# servocontroller.net
KiCad netlist of a schematic drawn in EAGLE
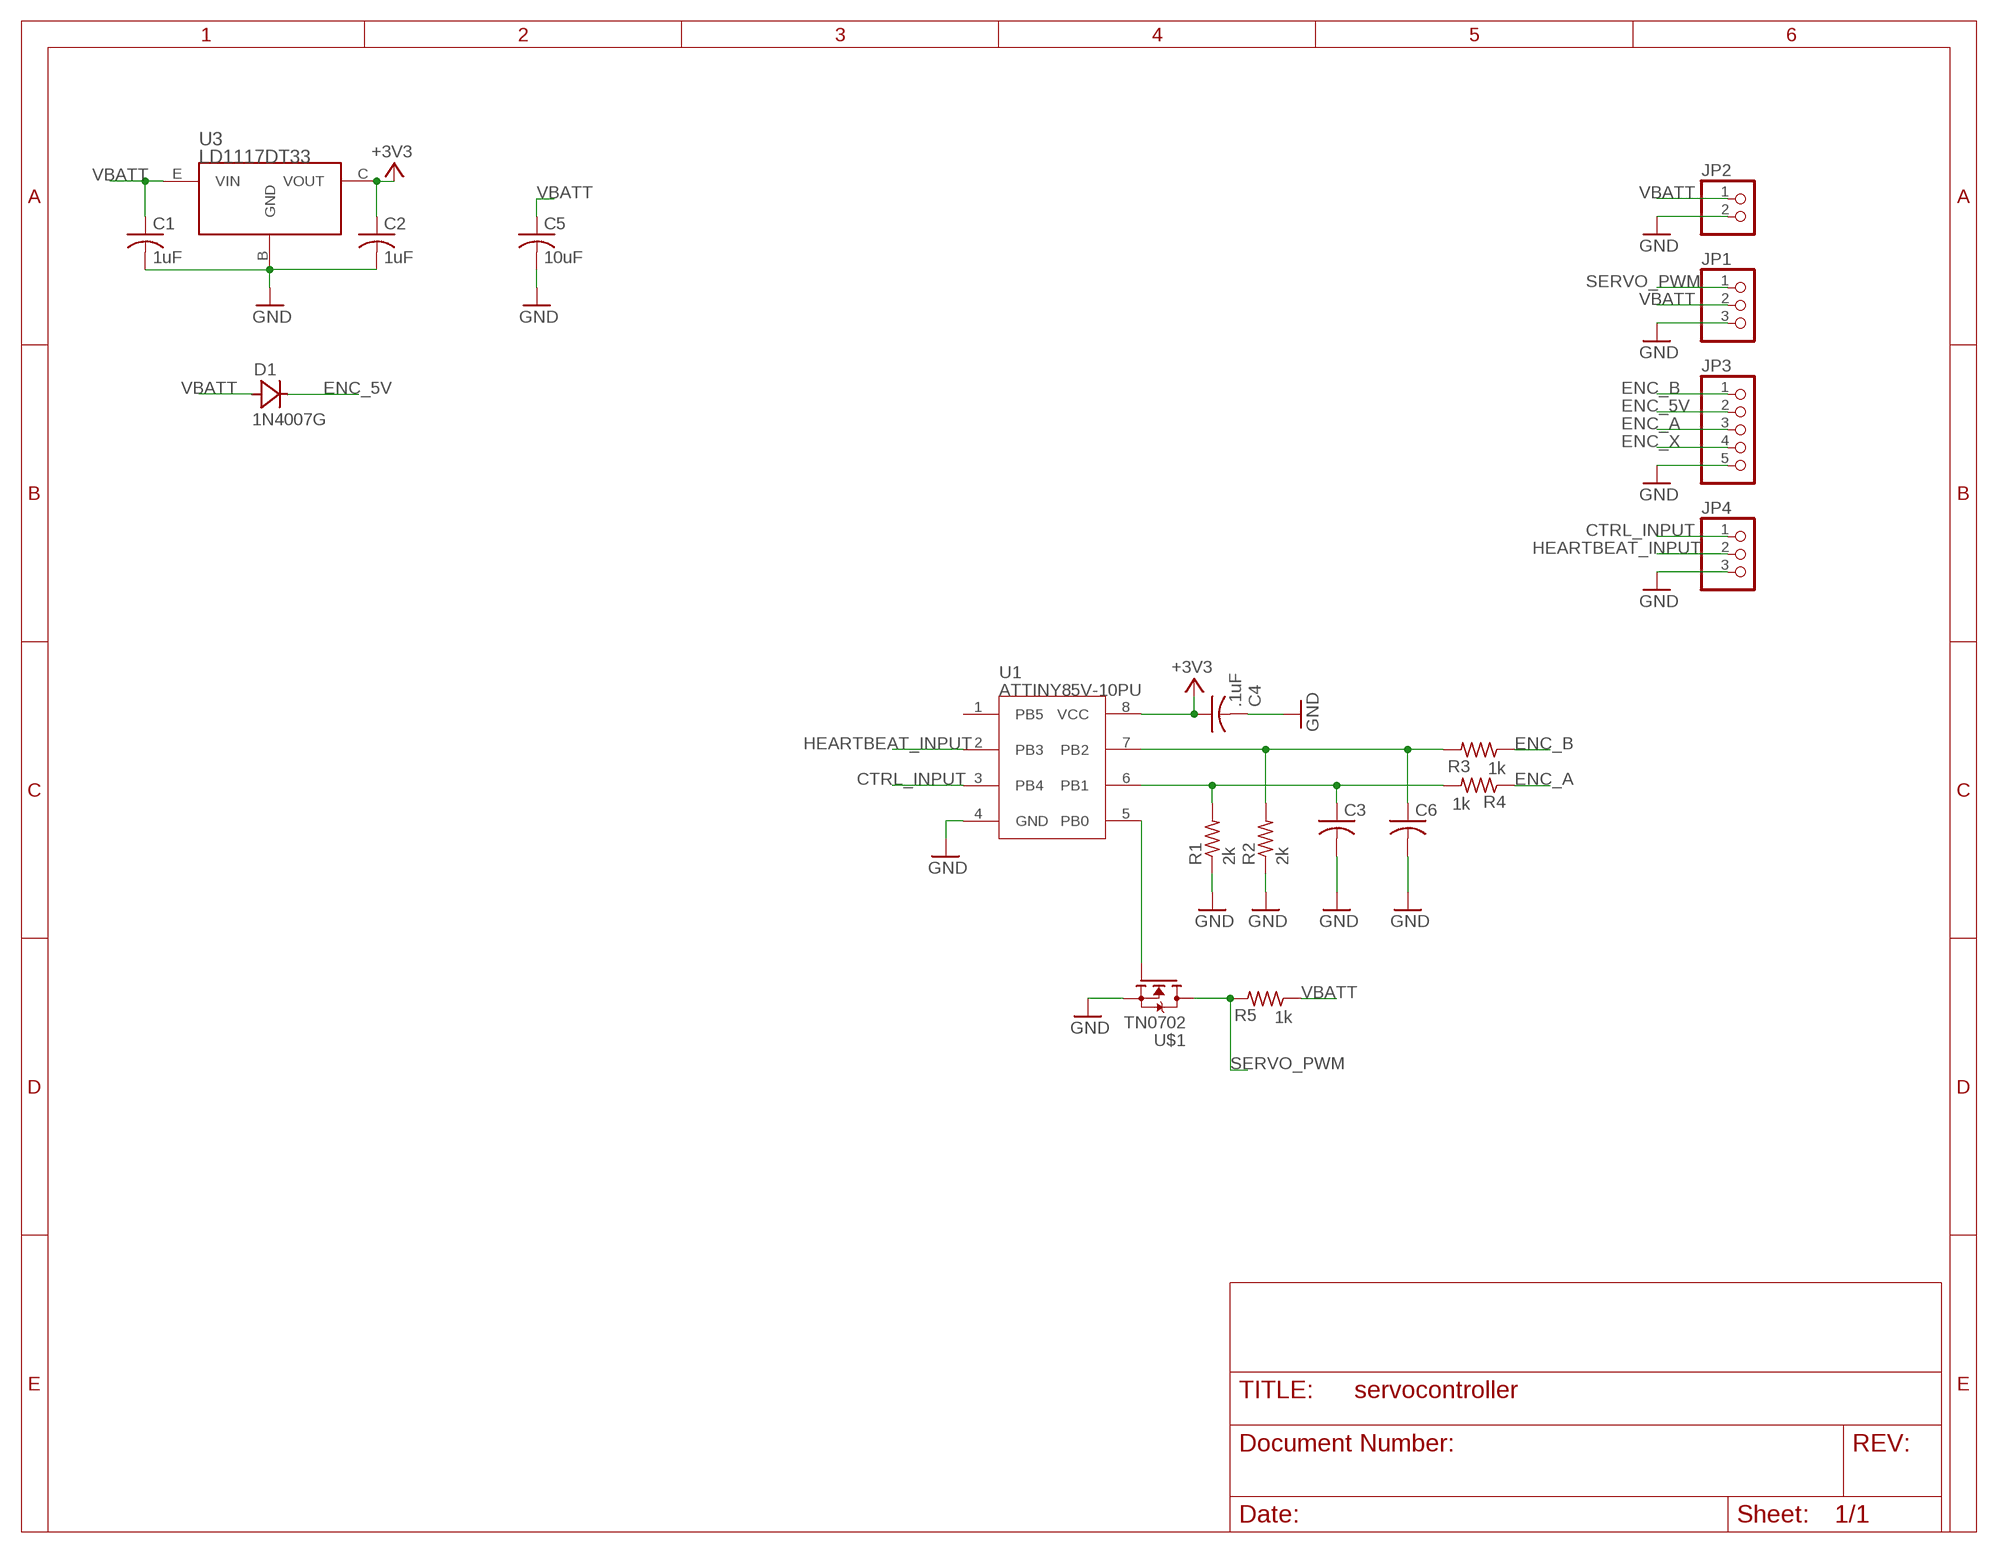
[diagram p0: schematic, sheet 1]

(export (version "E")
  (design (tool "Eeschema 10.0.6"))
  (components
    (comp (ref "C1")
      (value "1uF")
      (footprint "eagle-import:C0805")
      (libsource (lib "eagle-import") (part "C-USC0805"))
    )
    (comp (ref "C2")
      (value "1uF")
      (footprint "eagle-import:C0805")
      (libsource (lib "eagle-import") (part "C-USC0805"))
    )
    (comp (ref "C3")
      (value "C-USC0805")
      (footprint "eagle-import:C0805")
      (libsource (lib "eagle-import") (part "C-USC0805"))
    )
    (comp (ref "C4")
      (value ".1uF")
      (footprint "eagle-import:C0805")
      (libsource (lib "eagle-import") (part "C-USC0805"))
    )
    (comp (ref "C5")
      (value "10uF")
      (footprint "eagle-import:C0805")
      (libsource (lib "eagle-import") (part "C-USC0805"))
    )
    (comp (ref "C6")
      (value "C-USC0805")
      (footprint "eagle-import:C0805")
      (libsource (lib "eagle-import") (part "C-USC0805"))
    )
    (comp (ref "D1")
      (value "1N4007G")
      (footprint "eagle-import:DO35-7A")
      (libsource (lib "eagle-import") (part "1N4007G"))
    )
    (comp (ref "JP1")
      (value "PINHD-1X3")
      (footprint "eagle-import:1X03")
      (libsource (lib "eagle-import") (part "PINHD-1X3"))
    )
    (comp (ref "JP2")
      (value "PINHD-1X2")
      (footprint "eagle-import:1X02")
      (libsource (lib "eagle-import") (part "PINHD-1X2"))
    )
    (comp (ref "JP3")
      (value "PINHD-1X5")
      (footprint "eagle-import:1X05")
      (libsource (lib "eagle-import") (part "PINHD-1X5"))
    )
    (comp (ref "JP4")
      (value "PINHD-1X3")
      (footprint "eagle-import:1X03")
      (libsource (lib "eagle-import") (part "PINHD-1X3"))
    )
    (comp (ref "R1")
      (value "2k")
      (footprint "eagle-import:R0805")
      (libsource (lib "eagle-import") (part "R-US_R0805"))
    )
    (comp (ref "R2")
      (value "2k")
      (footprint "eagle-import:R0805")
      (libsource (lib "eagle-import") (part "R-US_R0805"))
    )
    (comp (ref "R3")
      (value "1k")
      (footprint "eagle-import:R0805")
      (libsource (lib "eagle-import") (part "R-US_R0805"))
    )
    (comp (ref "R4")
      (value "1k")
      (footprint "eagle-import:R0805")
      (libsource (lib "eagle-import") (part "R-US_R0805"))
    )
    (comp (ref "R5")
      (value "1k")
      (footprint "eagle-import:R0805")
      (libsource (lib "eagle-import") (part "R-US_R0805"))
    )
    (comp (ref "U$1")
      (value "TN0702")
      (footprint "eagle-import:TO92")
      (libsource (lib "eagle-import") (part "TN0702"))
    )
    (comp (ref "U1")
      (value "ATTINY85V-10PU")
      (footprint "eagle-import:DIL08")
      (libsource (lib "eagle-import") (part "ATTINY85V-10PU"))
    )
    (comp (ref "U3")
      (value "LD1117DT33")
      (footprint "eagle-import:DPACK_1")
      (libsource (lib "eagle-import") (part "LD1117DT33"))
    )
  )
  (nets
    (net (code "1") (name "+3V3") (class "Default")
      (node (ref "C2") (pin "1") (pinfunction "1_1") (pintype "passive"))
      (node (ref "C4") (pin "1") (pinfunction "1_1") (pintype "passive"))
      (node (ref "U1") (pin "8") (pinfunction "VCC_8") (pintype "bidirectional"))
      (node (ref "U3") (pin "C") (pinfunction "VOUT_C") (pintype "bidirectional"))
    )
    (net (code "2") (name "/CTRL_INPUT") (class "Default")
      (node (ref "JP4") (pin "1") (pinfunction "1_1") (pintype "passive"))
      (node (ref "U1") (pin "3") (pinfunction "PB4_3") (pintype "bidirectional"))
    )
    (net (code "3") (name "/ENC_5V") (class "Default")
      (node (ref "D1") (pin "C") (pinfunction "C_C") (pintype "passive"))
      (node (ref "JP3") (pin "2") (pinfunction "2_2") (pintype "passive"))
    )
    (net (code "4") (name "/ENC_A") (class "Default")
      (node (ref "JP3") (pin "3") (pinfunction "3_3") (pintype "passive"))
      (node (ref "R4") (pin "1") (pinfunction "1_1") (pintype "passive"))
    )
    (net (code "5") (name "/ENC_B") (class "Default")
      (node (ref "JP3") (pin "1") (pinfunction "1_1") (pintype "passive"))
      (node (ref "R3") (pin "1") (pinfunction "1_1") (pintype "passive"))
    )
    (net (code "6") (name "/ENC_X") (class "Default")
      (node (ref "JP3") (pin "4") (pinfunction "4_4") (pintype "passive"))
    )
    (net (code "7") (name "/HEARTBEAT_INPUT") (class "Default")
      (node (ref "JP4") (pin "2") (pinfunction "2_2") (pintype "passive"))
      (node (ref "U1") (pin "2") (pinfunction "PB3_2") (pintype "bidirectional"))
    )
    (net (code "8") (name "/SERVO_PWM") (class "Default")
      (node (ref "JP1") (pin "1") (pinfunction "1_1") (pintype "passive"))
      (node (ref "R5") (pin "2") (pinfunction "2_2") (pintype "passive"))
      (node (ref "U$1") (pin "1") (pinfunction "D_1") (pintype "passive"))
    )
    (net (code "9") (name "/VBATT") (class "Default")
      (node (ref "C1") (pin "1") (pinfunction "1_1") (pintype "passive"))
      (node (ref "C5") (pin "1") (pinfunction "1_1") (pintype "passive"))
      (node (ref "D1") (pin "A") (pinfunction "A_A") (pintype "passive"))
      (node (ref "JP1") (pin "2") (pinfunction "2_2") (pintype "passive"))
      (node (ref "JP2") (pin "1") (pinfunction "1_1") (pintype "passive"))
      (node (ref "R5") (pin "1") (pinfunction "1_1") (pintype "passive"))
      (node (ref "U3") (pin "E") (pinfunction "VIN_E") (pintype "bidirectional"))
    )
    (net (code "10") (name "GND") (class "Default")
      (node (ref "C1") (pin "2") (pinfunction "2_2") (pintype "passive"))
      (node (ref "C2") (pin "2") (pinfunction "2_2") (pintype "passive"))
      (node (ref "C3") (pin "2") (pinfunction "2_2") (pintype "passive"))
      (node (ref "C4") (pin "2") (pinfunction "2_2") (pintype "passive"))
      (node (ref "C5") (pin "2") (pinfunction "2_2") (pintype "passive"))
      (node (ref "C6") (pin "2") (pinfunction "2_2") (pintype "passive"))
      (node (ref "JP1") (pin "3") (pinfunction "3_3") (pintype "passive"))
      (node (ref "JP2") (pin "2") (pinfunction "2_2") (pintype "passive"))
      (node (ref "JP3") (pin "5") (pinfunction "5_5") (pintype "passive"))
      (node (ref "JP4") (pin "3") (pinfunction "3_3") (pintype "passive"))
      (node (ref "R1") (pin "1") (pinfunction "1_1") (pintype "passive"))
      (node (ref "R2") (pin "1") (pinfunction "1_1") (pintype "passive"))
      (node (ref "U$1") (pin "3") (pinfunction "S_3") (pintype "passive"))
      (node (ref "U1") (pin "4") (pinfunction "GND_4") (pintype "bidirectional"))
      (node (ref "U3") (pin "B") (pinfunction "GND_B") (pintype "bidirectional"))
    )
    (net (code "11") (name "Net-(U$1-G)") (class "Default")
      (node (ref "U$1") (pin "2") (pinfunction "G_2") (pintype "passive"))
      (node (ref "U1") (pin "5") (pinfunction "PB0_5") (pintype "bidirectional"))
    )
    (net (code "12") (name "Net-(U1-PB1)") (class "Default")
      (node (ref "C3") (pin "1") (pinfunction "1_1") (pintype "passive"))
      (node (ref "R1") (pin "2") (pinfunction "2_2") (pintype "passive"))
      (node (ref "R4") (pin "2") (pinfunction "2_2") (pintype "passive"))
      (node (ref "U1") (pin "6") (pinfunction "PB1_6") (pintype "bidirectional"))
    )
    (net (code "13") (name "Net-(U1-PB2)") (class "Default")
      (node (ref "C6") (pin "1") (pinfunction "1_1") (pintype "passive"))
      (node (ref "R2") (pin "2") (pinfunction "2_2") (pintype "passive"))
      (node (ref "R3") (pin "2") (pinfunction "2_2") (pintype "passive"))
      (node (ref "U1") (pin "7") (pinfunction "PB2_7") (pintype "bidirectional"))
    )
    (net (code "14") (name "unconnected-(U1-PB5-Pad1)") (class "Default")
      (node (ref "U1") (pin "1") (pinfunction "PB5_1") (pintype "bidirectional"))
    )
  )
)
